# Tacho_StdTeile.net
KiCad netlist of a schematic drawn in EAGLE
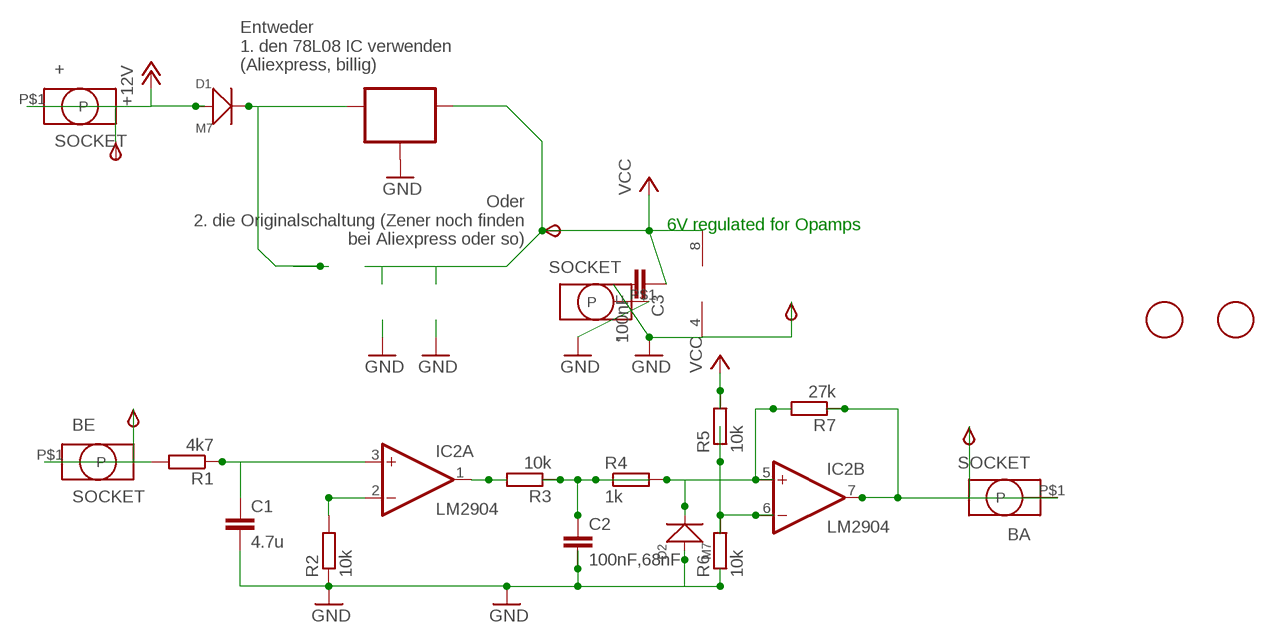
[diagram p0: schematic, sheet 1]

(export (version "E")
  (design (tool "Eeschema 10.0.6"))
  (components
    (comp (ref "+")
      (value "SOCKET")
      (footprint "eagle-import:ID2.5MM")
      (libsource (lib "eagle-import") (part "SOCKET"))
    )
    (comp (ref "+12V")
      (value "TPSB2.0")
      (footprint "eagle-import:B2.0")
      (libsource (lib "eagle-import") (part "TPSB2.0"))
    )
    (comp (ref "-")
      (value "SOCKET")
      (footprint "eagle-import:ID2.5MM")
      (libsource (lib "eagle-import") (part "SOCKET"))
    )
    (comp (ref "6V")
      (value "TPSB2.0")
      (footprint "eagle-import:B2.0")
      (libsource (lib "eagle-import") (part "TPSB2.0"))
    )
    (comp (ref "AUS")
      (value "TPSB2.0")
      (footprint "eagle-import:B2.0")
      (libsource (lib "eagle-import") (part "TPSB2.0"))
    )
    (comp (ref "BA")
      (value "SOCKET")
      (footprint "eagle-import:ID2.5MM")
      (libsource (lib "eagle-import") (part "SOCKET"))
    )
    (comp (ref "BE")
      (value "SOCKET")
      (footprint "eagle-import:ID2.5MM")
      (libsource (lib "eagle-import") (part "SOCKET"))
    )
    (comp (ref "C1")
      (value "4.7u")
      (footprint "eagle-import:C0805K")
      (libsource (lib "eagle-import") (part "C-EUC0805K"))
    )
    (comp (ref "C2")
      (value "100nF,68nF")
      (footprint "eagle-import:C0805K")
      (libsource (lib "eagle-import") (part "C-EUC0805K"))
    )
    (comp (ref "C3")
      (value "100nF")
      (footprint "eagle-import:C0805K")
      (libsource (lib "eagle-import") (part "C-EUC0805K"))
    )
    (comp (ref "D1")
      (value "M7")
      (footprint "eagle-import:DO-214AC")
      (fields (field (name "MPN") "1N4007"))
      (libsource (lib "eagle-import") (part "DIODE-GEN-PURPOSE-1KV-1A(DO-214AC)"))
    )
    (comp (ref "D2")
      (value "M7")
      (footprint "eagle-import:DO-214AC")
      (fields (field (name "MPN") "1N4007"))
      (libsource (lib "eagle-import") (part "DIODE-GEN-PURPOSE-1KV-1A(DO-214AC)"))
    )
    (comp (ref "EIN")
      (value "TPSB2.0")
      (footprint "eagle-import:B2.0")
      (libsource (lib "eagle-import") (part "TPSB2.0"))
    )
    (comp (ref "FID1")
      (value "FIDUCIAL")
      (footprint "eagle-import:FIDUCIAL_1MM")
      (libsource (lib "eagle-import") (part "FIDUCIAL"))
    )
    (comp (ref "FID2")
      (value "FIDUCIAL")
      (footprint "eagle-import:FIDUCIAL_1MM")
      (libsource (lib "eagle-import") (part "FIDUCIAL"))
    )
    (comp (ref "GND")
      (value "TPSB2.0")
      (footprint "eagle-import:B2.0")
      (libsource (lib "eagle-import") (part "TPSB2.0"))
    )
    (comp (ref "IC1")
      (value "5V/6V oder 8V Regler")
      (footprint "eagle-import:SOT89_ROUND")
      (libsource (lib "eagle-import") (part "78LXXSOT89_ROUND"))
    )
    (comp (ref "IC2")
      (value "LM2904")
      (footprint "eagle-import:SO08")
      (libsource (lib "eagle-import") (part "LM358D"))
    )
    (comp (ref "R1")
      (value "4k7")
      (footprint "eagle-import:R0805")
      (libsource (lib "eagle-import") (part "R-EU_R0805"))
    )
    (comp (ref "R2")
      (value "10k")
      (footprint "eagle-import:R0805")
      (libsource (lib "eagle-import") (part "R-EU_R0805"))
    )
    (comp (ref "R3")
      (value "10k")
      (footprint "eagle-import:R0805")
      (libsource (lib "eagle-import") (part "R-EU_R0805"))
    )
    (comp (ref "R4")
      (value "1k")
      (footprint "eagle-import:R0805")
      (libsource (lib "eagle-import") (part "R-EU_R0805"))
    )
    (comp (ref "R5")
      (value "10k")
      (footprint "eagle-import:R0805")
      (libsource (lib "eagle-import") (part "R-EU_R0805"))
    )
    (comp (ref "R6")
      (value "10k")
      (footprint "eagle-import:R0805")
      (libsource (lib "eagle-import") (part "R-EU_R0805"))
    )
    (comp (ref "R7")
      (value "27k")
      (footprint "eagle-import:R0805")
      (libsource (lib "eagle-import") (part "R-EU_R0805"))
    )
  )
  (nets
    (net (code "1") (name "+12V") (class "Default")
      (node (ref "+") (pin "P$1") (pinfunction "P_P$1") (pintype "bidirectional"))
      (node (ref "+12V") (pin "TP") (pinfunction "PP_TP") (pintype "input"))
      (node (ref "D1") (pin "1") (pinfunction "+_1") (pintype "passive"))
    )
    (net (code "2") (name "GND") (class "Default")
      (node (ref "-") (pin "P$1") (pinfunction "P_P$1") (pintype "bidirectional"))
      (node (ref "C1") (pin "2") (pinfunction "2_2") (pintype "passive"))
      (node (ref "C2") (pin "2") (pinfunction "2_2") (pintype "passive"))
      (node (ref "C3") (pin "2") (pinfunction "2_2") (pintype "passive"))
      (node (ref "D2") (pin "1") (pinfunction "+_1") (pintype "passive"))
      (node (ref "GND") (pin "TP") (pinfunction "PP_TP") (pintype "input"))
      (node (ref "IC1") (pin "2") (pinfunction "GND_2") (pintype "input"))
      (node (ref "IC1") (pin "2@1") (pinfunction "GND_2@1") (pintype "input"))
      (node (ref "IC2") (pin "4") (pinfunction "V-_4") (pintype "power_in"))
      (node (ref "R2") (pin "1") (pinfunction "1_1") (pintype "passive"))
      (node (ref "R6") (pin "1") (pinfunction "1_1") (pintype "passive"))
    )
    (net (code "3") (name "Net-(AUS-PP)") (class "Default")
      (node (ref "AUS") (pin "TP") (pinfunction "PP_TP") (pintype "input"))
      (node (ref "BA") (pin "P$1") (pinfunction "P_P$1") (pintype "bidirectional"))
      (node (ref "IC2") (pin "7") (pinfunction "OUT_7") (pintype "output"))
      (node (ref "R7") (pin "1") (pinfunction "1_1") (pintype "passive"))
    )
    (net (code "4") (name "Net-(BE-P)") (class "Default")
      (node (ref "BE") (pin "P$1") (pinfunction "P_P$1") (pintype "bidirectional"))
      (node (ref "EIN") (pin "TP") (pinfunction "PP_TP") (pintype "input"))
      (node (ref "R1") (pin "2") (pinfunction "2_2") (pintype "passive"))
    )
    (net (code "5") (name "Net-(C2-Pad1)") (class "Default")
      (node (ref "C2") (pin "1") (pinfunction "1_1") (pintype "passive"))
      (node (ref "R3") (pin "1") (pinfunction "1_1") (pintype "passive"))
      (node (ref "R4") (pin "1") (pinfunction "1_1") (pintype "passive"))
    )
    (net (code "6") (name "Net-(D1--)") (class "Default")
      (node (ref "D1") (pin "2") (pinfunction "-_2") (pintype "passive"))
      (node (ref "IC1") (pin "3") (pinfunction "IN_3") (pintype "input"))
    )
    (net (code "7") (name "Net-(D2--)") (class "Default")
      (node (ref "D2") (pin "2") (pinfunction "-_2") (pintype "passive"))
      (node (ref "IC2") (pin "5") (pinfunction "+IN_5") (pintype "input"))
      (node (ref "R4") (pin "2") (pinfunction "2_2") (pintype "passive"))
      (node (ref "R7") (pin "2") (pinfunction "2_2") (pintype "passive"))
    )
    (net (code "8") (name "Net-(IC2A-+IN)") (class "Default")
      (node (ref "C1") (pin "1") (pinfunction "1_1") (pintype "passive"))
      (node (ref "IC2") (pin "3") (pinfunction "+IN_3") (pintype "input"))
      (node (ref "R1") (pin "1") (pinfunction "1_1") (pintype "passive"))
    )
    (net (code "9") (name "Net-(IC2A--IN)") (class "Default")
      (node (ref "IC2") (pin "2") (pinfunction "-IN_2") (pintype "input"))
      (node (ref "R2") (pin "2") (pinfunction "2_2") (pintype "passive"))
    )
    (net (code "10") (name "Net-(IC2A-OUT)") (class "Default")
      (node (ref "IC2") (pin "1") (pinfunction "OUT_1") (pintype "output"))
      (node (ref "R3") (pin "2") (pinfunction "2_2") (pintype "passive"))
    )
    (net (code "11") (name "Net-(IC2B--IN)") (class "Default")
      (node (ref "IC2") (pin "6") (pinfunction "-IN_6") (pintype "input"))
      (node (ref "R5") (pin "1") (pinfunction "1_1") (pintype "passive"))
      (node (ref "R6") (pin "2") (pinfunction "2_2") (pintype "passive"))
    )
    (net (code "12") (name "VCC") (class "Default")
      (node (ref "6V") (pin "TP") (pinfunction "PP_TP") (pintype "input"))
      (node (ref "C3") (pin "1") (pinfunction "1_1") (pintype "passive"))
      (node (ref "IC1") (pin "1") (pinfunction "OUT_1") (pintype "passive"))
      (node (ref "IC2") (pin "8") (pinfunction "V+_8") (pintype "power_in"))
      (node (ref "R5") (pin "2") (pinfunction "2_2") (pintype "passive"))
    )
  )
)
